# InterfaceAndControl.net
KiCad netlist of a schematic drawn in Altium Designer
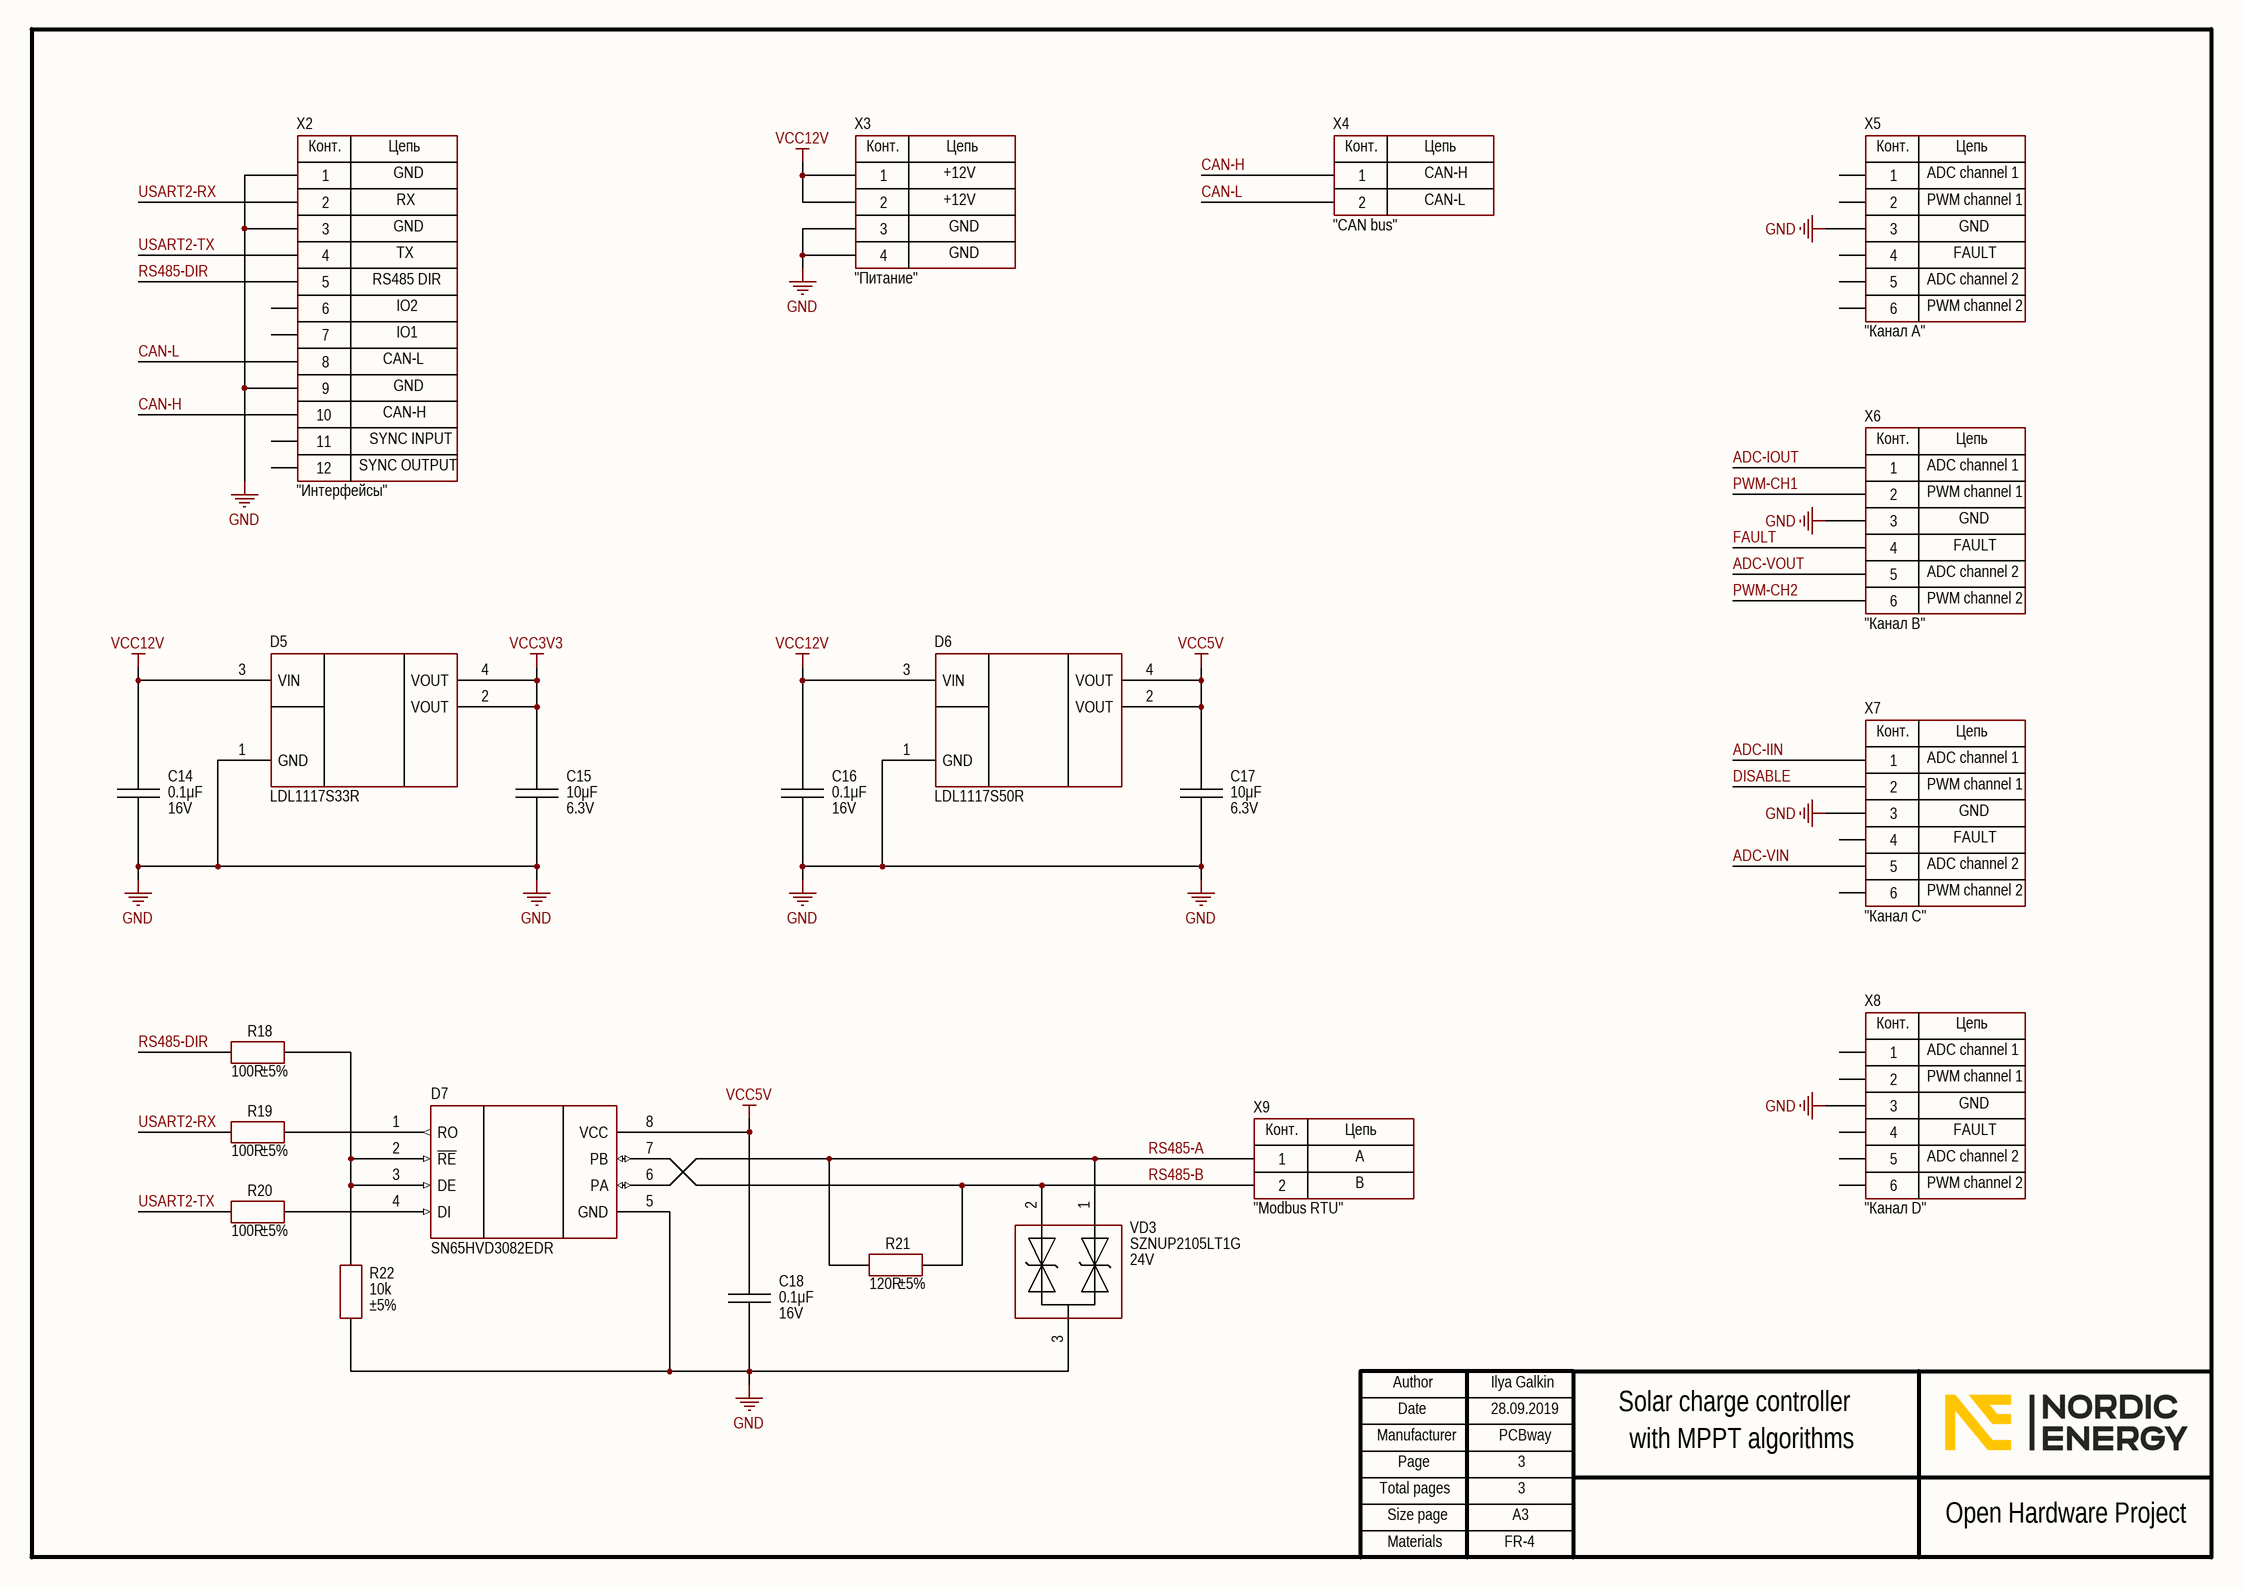
[diagram p0: InterfaceAndControl.SchDoc]

(export (version "E")
  (design (tool "Eeschema 10.0.6"))
  (components
    (comp (ref "C14")
      (value "0.1μF")
      (footprint "CAP: 0805")
      (fields
        (field (name "MANUFACTURER") "Yageo")
        (field (name "PARTNUMBER") "CC0805KRX7R7BB104")
        (field (name "VALUEMANUFACTURERPARTNUMBER") "Ceramic capacitor, 0.1μF, X7R, ±10%, 16V, 0805, -55...+125°C")
        (field (name "VOLTAGE") "16V")
      )
      (libsource (lib "Capacitor") (part "Ceramic_0805"))
    )
    (comp (ref "C15")
      (value "10μF")
      (footprint "CAP: 0805")
      (fields
        (field (name "MANUFACTURER") "Samsung")
        (field (name "PARTNUMBER") "CL21B106KQQNNNE")
        (field (name "VALUEMANUFACTURERPARTNUMBER") "Ceramic capacitor, 10μF, X7R, ±10%, 6.3V, 0805, -55...+125°C")
        (field (name "VOLTAGE") "6.3V")
      )
      (libsource (lib "Capacitor") (part "Ceramic_0805"))
    )
    (comp (ref "C16")
      (value "0.1μF")
      (footprint "CAP: 0805")
      (fields
        (field (name "MANUFACTURER") "Yageo")
        (field (name "PARTNUMBER") "CC0805KRX7R7BB104")
        (field (name "VALUEMANUFACTURERPARTNUMBER") "Ceramic capacitor, 0.1μF, X7R, ±10%, 16V, 0805, -55...+125°C")
        (field (name "VOLTAGE") "16V")
      )
      (libsource (lib "Capacitor") (part "Ceramic_0805"))
    )
    (comp (ref "C17")
      (value "10μF")
      (footprint "CAP: 0805")
      (fields
        (field (name "MANUFACTURER") "Samsung")
        (field (name "PARTNUMBER") "CL21B106KQQNNNE")
        (field (name "VALUEMANUFACTURERPARTNUMBER") "Ceramic capacitor, 10μF, X7R, ±10%, 6.3V, 0805, -55...+125°C")
        (field (name "VOLTAGE") "6.3V")
      )
      (libsource (lib "Capacitor") (part "Ceramic_0805"))
    )
    (comp (ref "C18")
      (value "0.1μF")
      (footprint "CAP: 0805")
      (fields
        (field (name "MANUFACTURER") "Yageo")
        (field (name "PARTNUMBER") "CC0805KRX7R7BB104")
        (field (name "VALUEMANUFACTURERPARTNUMBER") "Ceramic capacitor, 0.1μF, X7R, ±10%, 16V, 0805, -55...+125°C")
        (field (name "VOLTAGE") "16V")
      )
      (libsource (lib "Capacitor") (part "Ceramic_0805"))
    )
    (comp (ref "D5")
      (value "~")
      (footprint "SOT223")
      (description "Linear voltage regulator")
      (fields
        (field (name "MANUFACTURER") "STMicroelectronics")
        (field (name "VALUEMANUFACTURERPARTNUMBER") "Linear voltage regulator, input 3.9...18V, 0.6V, output 3.3V, 1.2A, -40...+85°C, SOT223")
        (field (name "PARTNUMBER") "LDL1117S33R")
      )
      (libsource (lib "IC. Power supply") (part "LDL1117S33R"))
    )
    (comp (ref "D6")
      (value "~")
      (footprint "SOT223")
      (description "Linear voltage regulator")
      (fields
        (field (name "MANUFACTURER") "STMicroelectronics")
        (field (name "VALUEMANUFACTURERPARTNUMBER") "Linear voltage regulator, input 5.6...18V, 0.6V, output 5V, 1.2A, -40...+85°C, SOT-223")
        (field (name "PARTNUMBER") "LDL1117S50R")
      )
      (libsource (lib "IC. Power supply") (part "LDL1117S33R"))
    )
    (comp (ref "D7")
      (value "~")
      (footprint "8-SOIC")
      (description "RS485")
      (fields
        (field (name "MANUFACTURER") "Texas Instruments")
        (field (name "VALUEMANUFACTURERPARTNUMBER") "IC RS485 transceiver, 200 kbps, Half-duplex, 4.5...5.5V, -40...+85°C, 8-SOIC")
        (field (name "PARTNUMBER") "SN65HVD3082EDR")
      )
      (libsource (lib "IC. Interface") (part "SN65HVD3082EDR"))
    )
    (comp (ref "R18")
      (value "100R")
      (footprint "RES: 0805")
      (fields
        (field (name "MANUFACTURER") "Yageo")
        (field (name "PARTNUMBER") "RC0805JR-07100RL")
        (field (name "VALUEMANUFACTURERPARTNUMBER") "Resistor film, 100R, ±5%, 0805, 0.125W, -55...+125°C")
        (field (name "TOLERANCE") "±5%")
      )
      (libsource (lib "Resistor") (part "Resistor_0805"))
    )
    (comp (ref "R19")
      (value "100R")
      (footprint "RES: 0805")
      (fields
        (field (name "MANUFACTURER") "Yageo")
        (field (name "PARTNUMBER") "RC0805JR-07100RL")
        (field (name "VALUEMANUFACTURERPARTNUMBER") "Resistor film, 100R, ±5%, 0805, 0.125W, -55...+125°C")
        (field (name "TOLERANCE") "±5%")
      )
      (libsource (lib "Resistor") (part "Resistor_0805"))
    )
    (comp (ref "R20")
      (value "100R")
      (footprint "RES: 0805")
      (fields
        (field (name "MANUFACTURER") "Yageo")
        (field (name "PARTNUMBER") "RC0805JR-07100RL")
        (field (name "VALUEMANUFACTURERPARTNUMBER") "Resistor film, 100R, ±5%, 0805, 0.125W, -55...+125°C")
        (field (name "TOLERANCE") "±5%")
      )
      (libsource (lib "Resistor") (part "Resistor_0805"))
    )
    (comp (ref "R21")
      (value "120R")
      (footprint "RES: 0805")
      (fields
        (field (name "MANUFACTURER") "Yageo")
        (field (name "PARTNUMBER") "RC0805JR-07120RL")
        (field (name "VALUEMANUFACTURERPARTNUMBER") "Resistor film, 120R, ±5%, 0805, 0.125W, -55...+125°C")
        (field (name "TOLERANCE") "±5%")
      )
      (libsource (lib "Resistor") (part "Resistor_0805"))
    )
    (comp (ref "R22")
      (value "10k")
      (footprint "RES: 0805")
      (fields
        (field (name "MANUFACTURER") "Yageo")
        (field (name "PARTNUMBER") "RC0805JR-0710KL")
        (field (name "VALUEMANUFACTURERPARTNUMBER") "Resistor film, 10k, ±5%, 0805, 0.125W, -55...+125°C")
        (field (name "TOLERANCE") "±5%")
      )
      (libsource (lib "") (part "Resistor_0805_1"))
    )
    (comp (ref "VD3")
      (value "~")
      (footprint "SOT23")
      (fields
        (field (name "MANUFACTURER") "ON Semiconductor")
        (field (name "VALUEMANUFACTURERPARTNUMBER") "TVS diode, 24V, 350W peak, 0.9V, 30pF, SOT-23, -55...+150°C")
        (field (name "VOLTAGE") "24V")
        (field (name "PARTNUMBER") "SZNUP2105LT1G")
      )
      (libsource (lib "Diode") (part "TVS_array"))
    )
    (comp (ref "X2")
      (value "~")
      (footprint "CON: PBD-12")
      (fields
        (field (name "MANUFACTURER") "Connfly")
        (field (name "VALUEMANUFACTURERPARTNUMBER") "Connector, 12pin, 2.54mm, 500VAC, 3A")
        (field (name "PARTNUMBER") "PBD-12")
        (field (name "COMMENTTEXT") "\"Интерфейсы\"")
      )
      (libsource (lib "Connector") (part "PBD-12"))
    )
    (comp (ref "X3")
      (value "~")
      (footprint "CON: PBD-4")
      (fields
        (field (name "MANUFACTURER") "Connfly")
        (field (name "VALUEMANUFACTURERPARTNUMBER") "Connector, 4pin, 2.54mm, 500VAC, 3A")
        (field (name "PARTNUMBER") "PBD-4")
        (field (name "COMMENTTEXT") "\"Питание\"")
      )
      (libsource (lib "Connector") (part "PBD-4"))
    )
    (comp (ref "X4")
      (value "~")
      (footprint "CON: DG350-3.5-02P")
      (fields
        (field (name "MANUFACTURER") "Degson")
        (field (name "VALUEMANUFACTURERPARTNUMBER") "Terminal connector, 2pin, 3.5mm, 300VAC, 10A")
        (field (name "PARTNUMBER") "DG350-3.5-02P-14")
        (field (name "COMMENTTEXT") "\"CAN bus\"")
      )
      (libsource (lib "Connector") (part "Connector_terminal_2pin"))
    )
    (comp (ref "X5")
      (value "~")
      (footprint "CON: PBD-6")
      (fields
        (field (name "MANUFACTURER") "Connfly")
        (field (name "VALUEMANUFACTURERPARTNUMBER") "Connector, 6pin, 2.54mm, 500VAC, 3A")
        (field (name "PARTNUMBER") "PBD-6")
        (field (name "COMMENTTEXT") "\"Канал А\"")
      )
      (libsource (lib "Connector") (part "PBD-6"))
    )
    (comp (ref "X6")
      (value "~")
      (footprint "CON: PBD-6")
      (fields
        (field (name "MANUFACTURER") "Connfly")
        (field (name "VALUEMANUFACTURERPARTNUMBER") "Connector, 6pin, 2.54mm, 500VAC, 3A")
        (field (name "PARTNUMBER") "PBD-6")
        (field (name "COMMENTTEXT") "\"Канал В\"")
      )
      (libsource (lib "Connector") (part "PBD-6"))
    )
    (comp (ref "X7")
      (value "~")
      (footprint "CON: PBD-6")
      (fields
        (field (name "MANUFACTURER") "Connfly")
        (field (name "VALUEMANUFACTURERPARTNUMBER") "Connector, 6pin, 2.54mm, 500VAC, 3A")
        (field (name "PARTNUMBER") "PBD-6")
        (field (name "COMMENTTEXT") "\"Канал С\"")
      )
      (libsource (lib "Connector") (part "PBD-6"))
    )
    (comp (ref "X8")
      (value "~")
      (footprint "CON: PBD-6")
      (fields
        (field (name "MANUFACTURER") "Connfly")
        (field (name "VALUEMANUFACTURERPARTNUMBER") "Connector, 6pin, 2.54mm, 500VAC, 3A")
        (field (name "PARTNUMBER") "PBD-6")
        (field (name "COMMENTTEXT") "\"Канал D\"")
      )
      (libsource (lib "Connector") (part "PBD-6"))
    )
    (comp (ref "X9")
      (value "~")
      (footprint "CON: DG350-3.5-02P")
      (fields
        (field (name "MANUFACTURER") "Degson")
        (field (name "VALUEMANUFACTURERPARTNUMBER") "Terminal connector, 2pin, 3.5mm, 300VAC, 10A")
        (field (name "PARTNUMBER") "DG350-3.5-02P-14")
        (field (name "COMMENTTEXT") "\"Modbus RTU\"")
      )
      (libsource (lib "Connector") (part "Connector_terminal_2pin"))
    )
  )
  (nets
    (net (code "1") (name "/ADC-IIN") (class "Default")
      (node (ref "X7") (pin "1") (pinfunction "1_1") (pintype "passive"))
    )
    (net (code "2") (name "/ADC-IOUT") (class "Default")
      (node (ref "X6") (pin "1") (pinfunction "1_1") (pintype "passive"))
    )
    (net (code "3") (name "/ADC-VIN") (class "Default")
      (node (ref "X7") (pin "5") (pinfunction "5_5") (pintype "power_in"))
    )
    (net (code "4") (name "/ADC-VOUT") (class "Default")
      (node (ref "X6") (pin "5") (pinfunction "5_5") (pintype "power_in"))
    )
    (net (code "5") (name "/CAN-H") (class "Default")
      (node (ref "X2") (pin "10") (pinfunction "10_10") (pintype "power_in"))
      (node (ref "X4") (pin "1") (pinfunction "1_1") (pintype "passive"))
    )
    (net (code "6") (name "/CAN-L") (class "Default")
      (node (ref "X2") (pin "8") (pinfunction "8_8") (pintype "power_in"))
      (node (ref "X4") (pin "2") (pinfunction "2_2") (pintype "passive"))
    )
    (net (code "7") (name "/DISABLE") (class "Default")
      (node (ref "X7") (pin "2") (pinfunction "2_2") (pintype "passive"))
    )
    (net (code "8") (name "/FAULT") (class "Default")
      (node (ref "X6") (pin "4") (pinfunction "4_4") (pintype "power_in"))
    )
    (net (code "9") (name "/PWM-CH1") (class "Default")
      (node (ref "X6") (pin "2") (pinfunction "2_2") (pintype "passive"))
    )
    (net (code "10") (name "/PWM-CH2") (class "Default")
      (node (ref "X6") (pin "6") (pinfunction "6_6") (pintype "power_in"))
    )
    (net (code "11") (name "/RS485-A") (class "Default")
      (node (ref "D7") (pin "6") (pinfunction "PA_6") (pintype "bidirectional"))
      (node (ref "R21") (pin "1") (pinfunction "1_1") (pintype "passive"))
      (node (ref "VD3") (pin "1") (pintype "passive"))
      (node (ref "X9") (pin "1") (pinfunction "1_1") (pintype "passive"))
    )
    (net (code "12") (name "/RS485-B") (class "Default")
      (node (ref "D7") (pin "7") (pinfunction "PB_7") (pintype "bidirectional"))
      (node (ref "R21") (pin "2") (pinfunction "2_2") (pintype "passive"))
      (node (ref "VD3") (pin "2") (pintype "passive"))
      (node (ref "X9") (pin "2") (pinfunction "2_2") (pintype "passive"))
    )
    (net (code "13") (name "/RS485-DIR") (class "Default")
      (node (ref "R18") (pin "1") (pinfunction "1_1") (pintype "passive"))
      (node (ref "X2") (pin "5") (pinfunction "5_5") (pintype "power_in"))
    )
    (net (code "14") (name "/USART2-RX") (class "Default")
      (node (ref "R19") (pin "1") (pinfunction "1_1") (pintype "passive"))
      (node (ref "X2") (pin "2") (pinfunction "2_2") (pintype "passive"))
    )
    (net (code "15") (name "/USART2-TX") (class "Default")
      (node (ref "R20") (pin "1") (pinfunction "1_1") (pintype "passive"))
      (node (ref "X2") (pin "4") (pinfunction "4_4") (pintype "power_in"))
    )
    (net (code "16") (name "GND") (class "Default")
      (node (ref "C14") (pin "1") (pinfunction "1_1") (pintype "power_in"))
      (node (ref "C15") (pin "1") (pinfunction "1_1") (pintype "power_in"))
      (node (ref "C16") (pin "1") (pinfunction "1_1") (pintype "power_in"))
      (node (ref "C17") (pin "1") (pinfunction "1_1") (pintype "power_in"))
      (node (ref "C18") (pin "1") (pinfunction "1_1") (pintype "power_in"))
      (node (ref "D5") (pin "1") (pinfunction "GND_1") (pintype "power_in"))
      (node (ref "D6") (pin "1") (pinfunction "GND_1") (pintype "power_in"))
      (node (ref "D7") (pin "5") (pinfunction "GND_5") (pintype "power_in"))
      (node (ref "R22") (pin "2") (pinfunction "2_2") (pintype "passive"))
      (node (ref "VD3") (pin "3") (pintype "passive"))
      (node (ref "X2") (pin "1") (pinfunction "1_1") (pintype "passive"))
      (node (ref "X2") (pin "3") (pinfunction "3_3") (pintype "power_in"))
      (node (ref "X2") (pin "9") (pinfunction "9_9") (pintype "power_in"))
      (node (ref "X3") (pin "3") (pinfunction "3_3") (pintype "power_in"))
      (node (ref "X3") (pin "4") (pinfunction "4_4") (pintype "power_in"))
      (node (ref "X5") (pin "3") (pinfunction "3_3") (pintype "power_in"))
      (node (ref "X6") (pin "3") (pinfunction "3_3") (pintype "power_in"))
      (node (ref "X7") (pin "3") (pinfunction "3_3") (pintype "power_in"))
      (node (ref "X8") (pin "3") (pinfunction "3_3") (pintype "power_in"))
    )
    (net (code "17") (name "Net-(D7-DE)") (class "Default")
      (node (ref "D7") (pin "2") (pinfunction "~{RE}_2") (pintype "input"))
      (node (ref "D7") (pin "3") (pinfunction "DE_3") (pintype "input"))
      (node (ref "R18") (pin "2") (pinfunction "2_2") (pintype "passive"))
      (node (ref "R22") (pin "1") (pinfunction "1_1") (pintype "passive"))
    )
    (net (code "18") (name "Net-(D7-DI)") (class "Default")
      (node (ref "D7") (pin "4") (pinfunction "DI_4") (pintype "input"))
      (node (ref "R20") (pin "2") (pinfunction "2_2") (pintype "passive"))
    )
    (net (code "19") (name "Net-(D7-RO)") (class "Default")
      (node (ref "D7") (pin "1") (pinfunction "RO_1") (pintype "output"))
      (node (ref "R19") (pin "2") (pinfunction "2_2") (pintype "passive"))
    )
    (net (code "20") (name "VCC3V3") (class "Default")
      (node (ref "C15") (pin "2") (pinfunction "2_2") (pintype "power_in"))
      (node (ref "D5") (pin "2") (pinfunction "VOUT_2") (pintype "power_in"))
      (node (ref "D5") (pin "4") (pinfunction "VOUT_4") (pintype "power_in"))
    )
    (net (code "21") (name "VCC5V") (class "Default")
      (node (ref "C17") (pin "2") (pinfunction "2_2") (pintype "power_in"))
      (node (ref "C18") (pin "2") (pinfunction "2_2") (pintype "power_in"))
      (node (ref "D6") (pin "2") (pinfunction "VOUT_2") (pintype "power_in"))
      (node (ref "D6") (pin "4") (pinfunction "VOUT_4") (pintype "power_in"))
      (node (ref "D7") (pin "8") (pinfunction "VCC_8") (pintype "power_in"))
    )
    (net (code "22") (name "VCC12V") (class "Default")
      (node (ref "C14") (pin "2") (pinfunction "2_2") (pintype "power_in"))
      (node (ref "C16") (pin "2") (pinfunction "2_2") (pintype "power_in"))
      (node (ref "D5") (pin "3") (pinfunction "VIN_3") (pintype "power_in"))
      (node (ref "D6") (pin "3") (pinfunction "VIN_3") (pintype "power_in"))
      (node (ref "X3") (pin "1") (pinfunction "1_1") (pintype "passive"))
      (node (ref "X3") (pin "2") (pinfunction "2_2") (pintype "passive"))
    )
    (net (code "23") (name "unconnected-(X2-Pad6)") (class "Default")
      (node (ref "X2") (pin "6") (pinfunction "6_6") (pintype "power_in"))
    )
    (net (code "24") (name "unconnected-(X2-Pad7)") (class "Default")
      (node (ref "X2") (pin "7") (pinfunction "7_7") (pintype "power_in"))
    )
    (net (code "25") (name "unconnected-(X2-Pad11)") (class "Default")
      (node (ref "X2") (pin "11") (pinfunction "11_11") (pintype "power_in"))
    )
    (net (code "26") (name "unconnected-(X2-Pad12)") (class "Default")
      (node (ref "X2") (pin "12") (pinfunction "12_12") (pintype "power_in"))
    )
    (net (code "27") (name "unconnected-(X5-Pad1)") (class "Default")
      (node (ref "X5") (pin "1") (pinfunction "1_1") (pintype "passive"))
    )
    (net (code "28") (name "unconnected-(X5-Pad2)") (class "Default")
      (node (ref "X5") (pin "2") (pinfunction "2_2") (pintype "passive"))
    )
    (net (code "29") (name "unconnected-(X5-Pad4)") (class "Default")
      (node (ref "X5") (pin "4") (pinfunction "4_4") (pintype "power_in"))
    )
    (net (code "30") (name "unconnected-(X5-Pad5)") (class "Default")
      (node (ref "X5") (pin "5") (pinfunction "5_5") (pintype "power_in"))
    )
    (net (code "31") (name "unconnected-(X5-Pad6)") (class "Default")
      (node (ref "X5") (pin "6") (pinfunction "6_6") (pintype "power_in"))
    )
    (net (code "32") (name "unconnected-(X7-Pad4)") (class "Default")
      (node (ref "X7") (pin "4") (pinfunction "4_4") (pintype "power_in"))
    )
    (net (code "33") (name "unconnected-(X7-Pad6)") (class "Default")
      (node (ref "X7") (pin "6") (pinfunction "6_6") (pintype "power_in"))
    )
    (net (code "34") (name "unconnected-(X8-Pad1)") (class "Default")
      (node (ref "X8") (pin "1") (pinfunction "1_1") (pintype "passive"))
    )
    (net (code "35") (name "unconnected-(X8-Pad2)") (class "Default")
      (node (ref "X8") (pin "2") (pinfunction "2_2") (pintype "passive"))
    )
    (net (code "36") (name "unconnected-(X8-Pad4)") (class "Default")
      (node (ref "X8") (pin "4") (pinfunction "4_4") (pintype "power_in"))
    )
    (net (code "37") (name "unconnected-(X8-Pad5)") (class "Default")
      (node (ref "X8") (pin "5") (pinfunction "5_5") (pintype "power_in"))
    )
    (net (code "38") (name "unconnected-(X8-Pad6)") (class "Default")
      (node (ref "X8") (pin "6") (pinfunction "6_6") (pintype "power_in"))
    )
  )
)
